# DIY_Shield.net
KiCad netlist of a schematic drawn in EAGLE
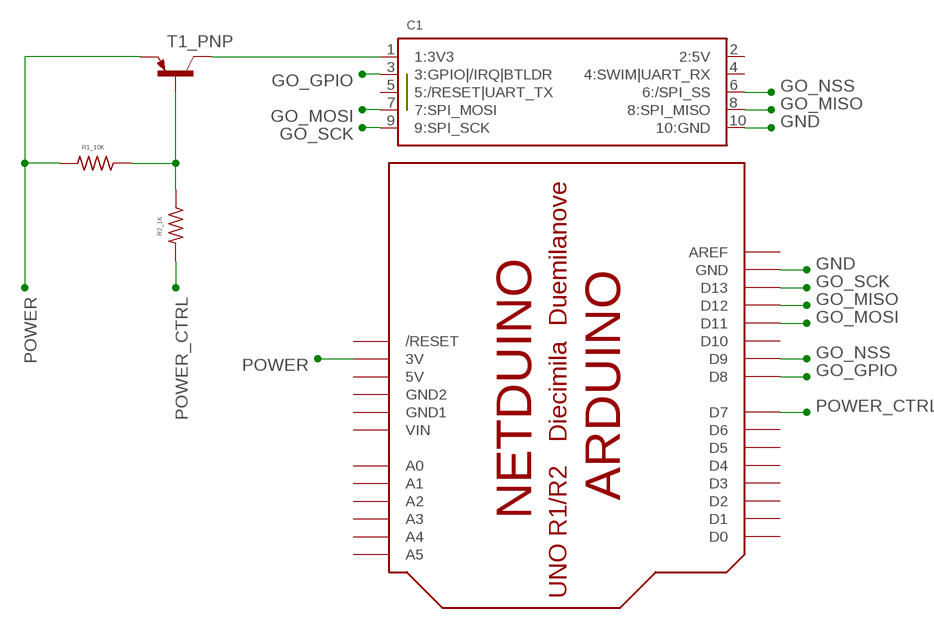
[diagram p0: schematic, sheet 1]

(export (version "E")
  (design (tool "Eeschema 10.0.6"))
  (components
    (comp (ref "C1")
      (value "GO_CONNECTOR")
      (footprint "eagle-import:FCI-1.27X1.27MM_10PIN_HEADER_SHROUDED_SMT")
      (libsource (lib "eagle-import") (part "GO_CONNECTOR"))
    )
    (comp (ref "NETDUINOSHIELD")
      (value "ARDUINOUNO")
      (footprint "eagle-import:ARDUINO")
      (libsource (lib "eagle-import") (part "ARDUINOUNO"))
    )
    (comp (ref "R1_10K")
      (value "RESISTOR_0805")
      (footprint "eagle-import:0805_NO_POLARITY")
      (libsource (lib "eagle-import") (part "RESISTOR_0805"))
    )
    (comp (ref "R2_1K")
      (value "RESISTOR_0805")
      (footprint "eagle-import:0805_NO_POLARITY")
      (libsource (lib "eagle-import") (part "RESISTOR_0805"))
    )
    (comp (ref "T1_PNP")
      (value "-PNP-TO92")
      (footprint "eagle-import:TO92")
      (libsource (lib "eagle-import") (part "-PNP-TO92"))
    )
  )
  (nets
    (net (code "1") (name "/5V") (class "Default")
      (node (ref "NETDUINOSHIELD") (pin "5V") (pinfunction "5V_5V") (pintype "power_in"))
    )
    (net (code "2") (name "/GND") (class "Default")
      (node (ref "C1") (pin "10") (pinfunction "10:GND_10") (pintype "passive"))
      (node (ref "NETDUINOSHIELD") (pin "GND") (pinfunction "GND_GND") (pintype "power_in"))
    )
    (net (code "3") (name "/GND1") (class "Default")
      (node (ref "NETDUINOSHIELD") (pin "GND1") (pinfunction "GND1_GND1") (pintype "power_in"))
    )
    (net (code "4") (name "/GND2") (class "Default")
      (node (ref "NETDUINOSHIELD") (pin "GND2") (pinfunction "GND2_GND2") (pintype "power_in"))
    )
    (net (code "5") (name "/GO_GPIO") (class "Default")
      (node (ref "C1") (pin "3") (pinfunction "3:GPIO|/IRQ|BTLDR_3") (pintype "bidirectional"))
      (node (ref "NETDUINOSHIELD") (pin "D8") (pinfunction "D8_D8") (pintype "bidirectional"))
    )
    (net (code "6") (name "/GO_MISO") (class "Default")
      (node (ref "C1") (pin "8") (pinfunction "8:SPI_MISO_8") (pintype "bidirectional"))
      (node (ref "NETDUINOSHIELD") (pin "D12") (pinfunction "D12_D12") (pintype "bidirectional"))
    )
    (net (code "7") (name "/GO_MOSI") (class "Default")
      (node (ref "C1") (pin "7") (pinfunction "7:SPI_MOSI_7") (pintype "bidirectional"))
      (node (ref "NETDUINOSHIELD") (pin "D11") (pinfunction "D11_D11") (pintype "bidirectional"))
    )
    (net (code "8") (name "/GO_NSS") (class "Default")
      (node (ref "C1") (pin "6") (pinfunction "6:/SPI_SS_6") (pintype "bidirectional"))
      (node (ref "NETDUINOSHIELD") (pin "D9") (pinfunction "D9_D9") (pintype "bidirectional"))
    )
    (net (code "9") (name "/GO_SCK") (class "Default")
      (node (ref "C1") (pin "9") (pinfunction "9:SPI_SCK_9") (pintype "bidirectional"))
      (node (ref "NETDUINOSHIELD") (pin "D13") (pinfunction "D13_D13") (pintype "bidirectional"))
    )
    (net (code "10") (name "/POWER") (class "Default")
      (node (ref "NETDUINOSHIELD") (pin "3V") (pinfunction "3V_3V") (pintype "power_in"))
      (node (ref "R1_10K") (pin "2") (pinfunction "2_2") (pintype "passive"))
      (node (ref "T1_PNP") (pin "1") (pinfunction "E_1") (pintype "passive"))
    )
    (net (code "11") (name "/POWER_CTRL") (class "Default")
      (node (ref "NETDUINOSHIELD") (pin "D7") (pinfunction "D7_D7") (pintype "bidirectional"))
      (node (ref "R2_1K") (pin "2") (pinfunction "2_2") (pintype "passive"))
    )
    (net (code "12") (name "/VIN") (class "Default")
      (node (ref "NETDUINOSHIELD") (pin "VIN") (pinfunction "VIN_VIN") (pintype "power_in"))
    )
    (net (code "13") (name "Net-(C1-1:3V3)") (class "Default")
      (node (ref "C1") (pin "1") (pinfunction "1:3V3_1") (pintype "power_in"))
      (node (ref "T1_PNP") (pin "3") (pinfunction "C_3") (pintype "passive"))
    )
    (net (code "14") (name "Net-(T1_PNP-B)") (class "Default")
      (node (ref "R1_10K") (pin "1") (pinfunction "1_1") (pintype "passive"))
      (node (ref "R2_1K") (pin "1") (pinfunction "1_1") (pintype "passive"))
      (node (ref "T1_PNP") (pin "2") (pinfunction "B_2") (pintype "passive"))
    )
    (net (code "15") (name "unconnected-(C1-2:5V-Pad2)") (class "Default")
      (node (ref "C1") (pin "2") (pinfunction "2:5V_2") (pintype "power_in"))
    )
    (net (code "16") (name "unconnected-(C1-4:SWIM|UART_RX-Pad4)") (class "Default")
      (node (ref "C1") (pin "4") (pinfunction "4:SWIM|UART_RX_4") (pintype "bidirectional"))
    )
    (net (code "17") (name "unconnected-(C1-5:{slash}RESET|UART_TX-Pad5)") (class "Default")
      (node (ref "C1") (pin "5") (pinfunction "5:/RESET|UART_TX_5") (pintype "bidirectional"))
    )
    (net (code "18") (name "unconnected-(NETDUINOSHIELD-PadA0)") (class "Default")
      (node (ref "NETDUINOSHIELD") (pin "A0") (pinfunction "A0_A0") (pintype "bidirectional"))
    )
    (net (code "19") (name "unconnected-(NETDUINOSHIELD-PadA1)") (class "Default")
      (node (ref "NETDUINOSHIELD") (pin "A1") (pinfunction "A1_A1") (pintype "bidirectional"))
    )
    (net (code "20") (name "unconnected-(NETDUINOSHIELD-PadA2)") (class "Default")
      (node (ref "NETDUINOSHIELD") (pin "A2") (pinfunction "A2_A2") (pintype "bidirectional"))
    )
    (net (code "21") (name "unconnected-(NETDUINOSHIELD-PadA3)") (class "Default")
      (node (ref "NETDUINOSHIELD") (pin "A3") (pinfunction "A3_A3") (pintype "bidirectional"))
    )
    (net (code "22") (name "unconnected-(NETDUINOSHIELD-PadA4)") (class "Default")
      (node (ref "NETDUINOSHIELD") (pin "A4") (pinfunction "A4_A4") (pintype "bidirectional"))
    )
    (net (code "23") (name "unconnected-(NETDUINOSHIELD-PadA5)") (class "Default")
      (node (ref "NETDUINOSHIELD") (pin "A5") (pinfunction "A5_A5") (pintype "bidirectional"))
    )
    (net (code "24") (name "unconnected-(NETDUINOSHIELD-PadAREF)") (class "Default")
      (node (ref "NETDUINOSHIELD") (pin "AREF") (pinfunction "AREF_AREF") (pintype "bidirectional"))
    )
    (net (code "25") (name "unconnected-(NETDUINOSHIELD-PadD0)") (class "Default")
      (node (ref "NETDUINOSHIELD") (pin "D0") (pinfunction "D0_D0") (pintype "bidirectional"))
    )
    (net (code "26") (name "unconnected-(NETDUINOSHIELD-PadD1)") (class "Default")
      (node (ref "NETDUINOSHIELD") (pin "D1") (pinfunction "D1_D1") (pintype "bidirectional"))
    )
    (net (code "27") (name "unconnected-(NETDUINOSHIELD-PadD2)") (class "Default")
      (node (ref "NETDUINOSHIELD") (pin "D2") (pinfunction "D2_D2") (pintype "bidirectional"))
    )
    (net (code "28") (name "unconnected-(NETDUINOSHIELD-PadD3)") (class "Default")
      (node (ref "NETDUINOSHIELD") (pin "D3") (pinfunction "D3_D3") (pintype "bidirectional"))
    )
    (net (code "29") (name "unconnected-(NETDUINOSHIELD-PadD4)") (class "Default")
      (node (ref "NETDUINOSHIELD") (pin "D4") (pinfunction "D4_D4") (pintype "bidirectional"))
    )
    (net (code "30") (name "unconnected-(NETDUINOSHIELD-PadD5)") (class "Default")
      (node (ref "NETDUINOSHIELD") (pin "D5") (pinfunction "D5_D5") (pintype "bidirectional"))
    )
    (net (code "31") (name "unconnected-(NETDUINOSHIELD-PadD6)") (class "Default")
      (node (ref "NETDUINOSHIELD") (pin "D6") (pinfunction "D6_D6") (pintype "bidirectional"))
    )
    (net (code "32") (name "unconnected-(NETDUINOSHIELD-PadD10)") (class "Default")
      (node (ref "NETDUINOSHIELD") (pin "D10") (pinfunction "D10_D10") (pintype "bidirectional"))
    )
    (net (code "33") (name "unconnected-(NETDUINOSHIELD-{slash}RESET-PadRESET)") (class "Default")
      (node (ref "NETDUINOSHIELD") (pin "RESET") (pinfunction "/RESET_RESET") (pintype "bidirectional"))
    )
  )
)
